# JoyPad.net
KiCad netlist of a schematic drawn in EAGLE
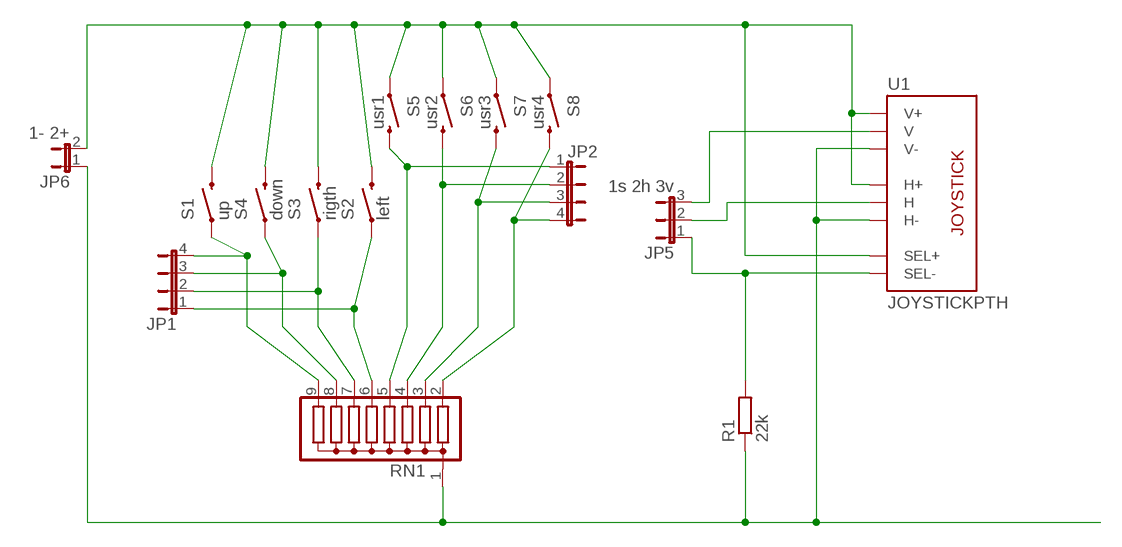
[diagram p0: schematic, sheet 1]

(export (version "E")
  (design (tool "Eeschema 10.0.6"))
  (components
    (comp (ref "JP1")
      (value "JP4E")
      (footprint "eagle-import:JP4")
      (libsource (lib "eagle-import") (part "JP4E"))
    )
    (comp (ref "JP2")
      (value "JP4E")
      (footprint "eagle-import:JP4")
      (libsource (lib "eagle-import") (part "JP4E"))
    )
    (comp (ref "JP5")
      (value "1s 2h 3v")
      (footprint "eagle-import:JP2")
      (libsource (lib "eagle-import") (part "JP2E"))
    )
    (comp (ref "JP6")
      (value "1- 2+")
      (footprint "eagle-import:JP1")
      (libsource (lib "eagle-import") (part "JP1E"))
    )
    (comp (ref "R1")
      (value "22k")
      (footprint "eagle-import:0207_15")
      (libsource (lib "eagle-import") (part "R-EU_0207/15"))
    )
    (comp (ref "RN1")
      (value "G08R")
      (footprint "eagle-import:SIL9")
      (libsource (lib "eagle-import") (part "G08R"))
    )
    (comp (ref "S1")
      (value "up")
      (footprint "eagle-import:TACTILE-PTH")
      (libsource (lib "eagle-import") (part "SWITCH-MOMENTARY-2PTH"))
    )
    (comp (ref "S2")
      (value "left")
      (footprint "eagle-import:TACTILE-PTH")
      (libsource (lib "eagle-import") (part "SWITCH-MOMENTARY-2PTH"))
    )
    (comp (ref "S3")
      (value "rigth")
      (footprint "eagle-import:TACTILE-PTH")
      (libsource (lib "eagle-import") (part "SWITCH-MOMENTARY-2PTH"))
    )
    (comp (ref "S4")
      (value "down")
      (footprint "eagle-import:TACTILE-PTH")
      (libsource (lib "eagle-import") (part "SWITCH-MOMENTARY-2PTH"))
    )
    (comp (ref "S5")
      (value "usr1")
      (footprint "eagle-import:TACTILE-PTH")
      (libsource (lib "eagle-import") (part "SWITCH-MOMENTARY-2PTH"))
    )
    (comp (ref "S6")
      (value "usr2")
      (footprint "eagle-import:TACTILE-PTH")
      (libsource (lib "eagle-import") (part "SWITCH-MOMENTARY-2PTH"))
    )
    (comp (ref "S7")
      (value "usr3")
      (footprint "eagle-import:TACTILE-PTH")
      (libsource (lib "eagle-import") (part "SWITCH-MOMENTARY-2PTH"))
    )
    (comp (ref "S8")
      (value "usr4")
      (footprint "eagle-import:TACTILE-PTH")
      (libsource (lib "eagle-import") (part "SWITCH-MOMENTARY-2PTH"))
    )
    (comp (ref "U1")
      (value "JOYSTICKPTH")
      (footprint "eagle-import:JOYSTICK")
      (libsource (lib "eagle-import") (part "JOYSTICKPTH"))
    )
  )
  (nets
    (net (code "1") (name "Net-(JP1-Pad1)") (class "Default")
      (node (ref "JP1") (pin "1") (pinfunction "1_1") (pintype "passive"))
      (node (ref "RN1") (pin "6") (pinfunction "6_6") (pintype "passive"))
      (node (ref "S2") (pin "1") (pinfunction "1_1") (pintype "passive"))
    )
    (net (code "2") (name "Net-(JP1-Pad2)") (class "Default")
      (node (ref "JP1") (pin "2") (pinfunction "2_2") (pintype "passive"))
      (node (ref "RN1") (pin "7") (pinfunction "7_7") (pintype "passive"))
      (node (ref "S3") (pin "1") (pinfunction "1_1") (pintype "passive"))
    )
    (net (code "3") (name "Net-(JP1-Pad3)") (class "Default")
      (node (ref "JP1") (pin "3") (pinfunction "3_3") (pintype "passive"))
      (node (ref "RN1") (pin "8") (pinfunction "8_8") (pintype "passive"))
      (node (ref "S4") (pin "1") (pinfunction "1_1") (pintype "passive"))
    )
    (net (code "4") (name "Net-(JP1-Pad4)") (class "Default")
      (node (ref "JP1") (pin "4") (pinfunction "4_4") (pintype "passive"))
      (node (ref "RN1") (pin "9") (pinfunction "9_9") (pintype "passive"))
      (node (ref "S1") (pin "1") (pinfunction "1_1") (pintype "passive"))
    )
    (net (code "5") (name "Net-(S1-2)") (class "Default")
      (node (ref "JP6") (pin "2") (pinfunction "2_2") (pintype "passive"))
      (node (ref "S1") (pin "3") (pinfunction "2_3") (pintype "passive"))
      (node (ref "S2") (pin "3") (pinfunction "2_3") (pintype "passive"))
      (node (ref "S3") (pin "3") (pinfunction "2_3") (pintype "passive"))
      (node (ref "S4") (pin "3") (pinfunction "2_3") (pintype "passive"))
      (node (ref "S5") (pin "1") (pinfunction "1_1") (pintype "passive"))
      (node (ref "S6") (pin "1") (pinfunction "1_1") (pintype "passive"))
      (node (ref "S7") (pin "1") (pinfunction "1_1") (pintype "passive"))
      (node (ref "S8") (pin "1") (pinfunction "1_1") (pintype "passive"))
      (node (ref "U1") (pin "B1A") (pinfunction "SEL+_B1A") (pintype "bidirectional"))
      (node (ref "U1") (pin "H1") (pinfunction "H+_H1") (pintype "bidirectional"))
      (node (ref "U1") (pin "V1") (pinfunction "V+_V1") (pintype "bidirectional"))
    )
    (net (code "6") (name "Net-(S5-2)") (class "Default")
      (node (ref "JP2") (pin "1") (pinfunction "1_1") (pintype "passive"))
      (node (ref "RN1") (pin "5") (pinfunction "5_5") (pintype "passive"))
      (node (ref "S5") (pin "3") (pinfunction "2_3") (pintype "passive"))
    )
    (net (code "7") (name "Net-(S6-2)") (class "Default")
      (node (ref "JP2") (pin "2") (pinfunction "2_2") (pintype "passive"))
      (node (ref "RN1") (pin "4") (pinfunction "4_4") (pintype "passive"))
      (node (ref "S6") (pin "3") (pinfunction "2_3") (pintype "passive"))
    )
    (net (code "8") (name "Net-(S7-2)") (class "Default")
      (node (ref "JP2") (pin "3") (pinfunction "3_3") (pintype "passive"))
      (node (ref "RN1") (pin "3") (pinfunction "3_3") (pintype "passive"))
      (node (ref "S7") (pin "3") (pinfunction "2_3") (pintype "passive"))
    )
    (net (code "9") (name "Net-(S8-2)") (class "Default")
      (node (ref "JP2") (pin "4") (pinfunction "4_4") (pintype "passive"))
      (node (ref "RN1") (pin "2") (pinfunction "2_2") (pintype "passive"))
      (node (ref "S8") (pin "3") (pinfunction "2_3") (pintype "passive"))
    )
    (net (code "10") (name "Net-(U1-H)") (class "Default")
      (node (ref "JP5") (pin "2") (pinfunction "2_2") (pintype "passive"))
      (node (ref "U1") (pin "H2") (pinfunction "H_H2") (pintype "bidirectional"))
    )
    (net (code "11") (name "Net-(U1-H-)") (class "Default")
      (node (ref "JP6") (pin "1") (pinfunction "1_1") (pintype "passive"))
      (node (ref "R1") (pin "1") (pinfunction "1_1") (pintype "passive"))
      (node (ref "RN1") (pin "1") (pinfunction "1_1") (pintype "passive"))
      (node (ref "U1") (pin "H3") (pinfunction "H-_H3") (pintype "bidirectional"))
      (node (ref "U1") (pin "V3") (pinfunction "V-_V3") (pintype "bidirectional"))
    )
    (net (code "12") (name "Net-(U1-SEL-)") (class "Default")
      (node (ref "JP5") (pin "1") (pinfunction "1_1") (pintype "passive"))
      (node (ref "R1") (pin "2") (pinfunction "2_2") (pintype "passive"))
      (node (ref "U1") (pin "B2A") (pinfunction "SEL-_B2A") (pintype "bidirectional"))
    )
    (net (code "13") (name "Net-(U1-V)") (class "Default")
      (node (ref "JP5") (pin "3") (pinfunction "3_3") (pintype "passive"))
      (node (ref "U1") (pin "V2") (pinfunction "V_V2") (pintype "bidirectional"))
    )
  )
)
